# Helepolis_Level1.net
KiCad netlist of a schematic drawn in EAGLE
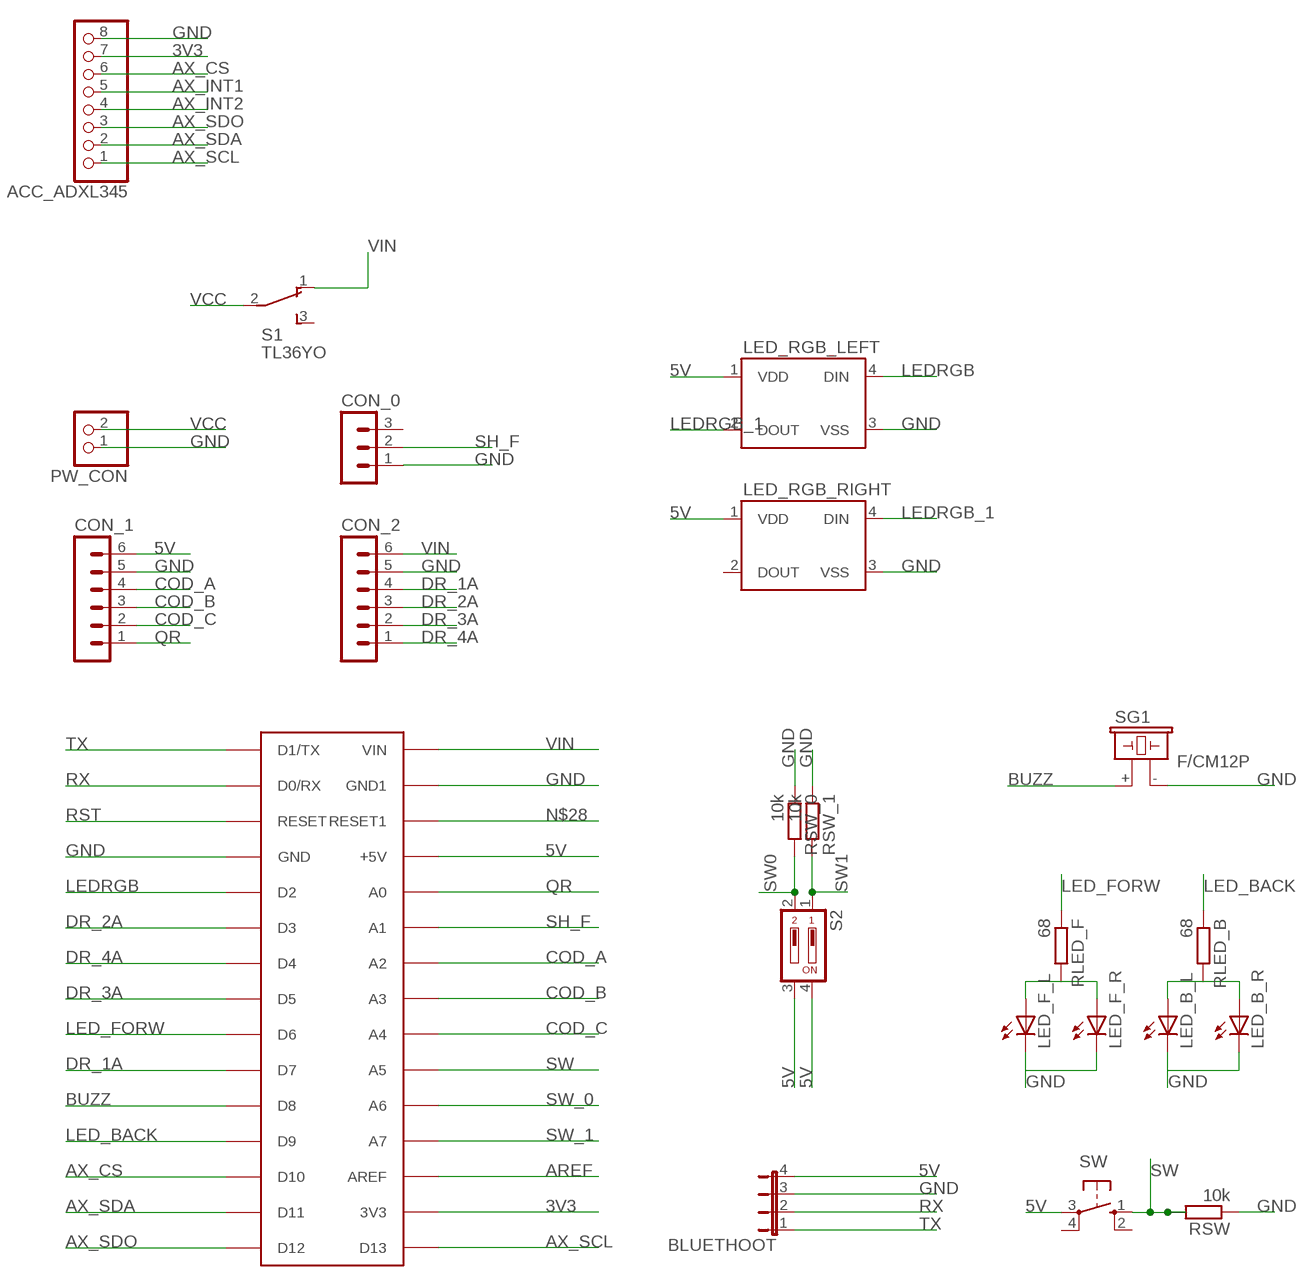
[diagram p0: schematic, sheet 1]

(export (version "E")
  (design (tool "Eeschema 10.0.6"))
  (components
    (comp (ref "ACC_ADXL345")
      (value "PINHD-1X8")
      (footprint "eagle-import:1X08")
      (libsource (lib "eagle-import") (part "PINHD-1X8"))
    )
    (comp (ref "BLUETHOOT")
      (value "JP4E")
      (footprint "eagle-import:JP4")
      (libsource (lib "eagle-import") (part "JP4E"))
    )
    (comp (ref "CON_0")
      (value "MA03-1")
      (footprint "eagle-import:MA03-1")
      (libsource (lib "eagle-import") (part "MA03-1"))
    )
    (comp (ref "CON_1")
      (value "MA06-1")
      (footprint "eagle-import:MA06-1")
      (libsource (lib "eagle-import") (part "MA06-1"))
    )
    (comp (ref "CON_2")
      (value "MA06-1")
      (footprint "eagle-import:MA06-1")
      (libsource (lib "eagle-import") (part "MA06-1"))
    )
    (comp (ref "LED_B_L")
      (value "LED5MM")
      (footprint "eagle-import:LED5MM")
      (libsource (lib "eagle-import") (part "LED5MM"))
    )
    (comp (ref "LED_B_R")
      (value "LED5MM")
      (footprint "eagle-import:LED5MM")
      (libsource (lib "eagle-import") (part "LED5MM"))
    )
    (comp (ref "LED_F_L")
      (value "LED5MM")
      (footprint "eagle-import:LED5MM")
      (libsource (lib "eagle-import") (part "LED5MM"))
    )
    (comp (ref "LED_F_R")
      (value "LED5MM")
      (footprint "eagle-import:LED5MM")
      (libsource (lib "eagle-import") (part "LED5MM"))
    )
    (comp (ref "LED_RGB_LEFT")
      (value "WS2812B")
      (footprint "eagle-import:WS2812B")
      (libsource (lib "eagle-import") (part "WS2812B"))
    )
    (comp (ref "LED_RGB_RIGHT")
      (value "WS2812B")
      (footprint "eagle-import:WS2812B")
      (libsource (lib "eagle-import") (part "WS2812B"))
    )
    (comp (ref "PW_CON")
      (value "PINHD-1X2")
      (footprint "eagle-import:1X02")
      (libsource (lib "eagle-import") (part "PINHD-1X2"))
    )
    (comp (ref "RLED_B")
      (value "68")
      (footprint "eagle-import:R1206")
      (libsource (lib "eagle-import") (part "R-EU_R1206"))
    )
    (comp (ref "RLED_F")
      (value "68")
      (footprint "eagle-import:R1206")
      (libsource (lib "eagle-import") (part "R-EU_R1206"))
    )
    (comp (ref "RSW")
      (value "10k")
      (footprint "eagle-import:R1206")
      (libsource (lib "eagle-import") (part "R-EU_R1206"))
    )
    (comp (ref "RSW_0")
      (value "10k")
      (footprint "eagle-import:R1206")
      (libsource (lib "eagle-import") (part "R-EU_R1206"))
    )
    (comp (ref "RSW_1")
      (value "10k")
      (footprint "eagle-import:R1206")
      (libsource (lib "eagle-import") (part "R-EU_R1206"))
    )
    (comp (ref "S1")
      (value "TL36YO")
      (footprint "eagle-import:TL3XYO")
      (libsource (lib "eagle-import") (part "TL36YO"))
    )
    (comp (ref "S2")
      (value "DP02")
      (footprint "eagle-import:DP-02")
      (fields (field (name "MPN") "MCDP02"))
      (libsource (lib "eagle-import") (part "DP02"))
    )
    (comp (ref "SG1")
      (value "F/CM12P")
      (footprint "eagle-import:F_CM12P")
      (libsource (lib "eagle-import") (part "F/CM12P"))
    )
    (comp (ref "SW")
      (value "10-XX")
      (footprint "eagle-import:B3F-10XX")
      (fields (field (name "MPN") "B3F-1000"))
      (libsource (lib "eagle-import") (part "10-XX"))
    )
    (comp (ref "U$1")
      (value "ARDUINONANO")
      (footprint "eagle-import:PDIP-32")
      (libsource (lib "eagle-import") (part "ARDUINONANO"))
    )
  )
  (nets
    (net (code "1") (name "/3V3") (class "Default")
      (node (ref "ACC_ADXL345") (pin "7") (pinfunction "7_7") (pintype "passive"))
      (node (ref "U$1") (pin "3V3") (pinfunction "3V3_3V3") (pintype "bidirectional"))
    )
    (net (code "2") (name "/5V") (class "Default")
      (node (ref "BLUETHOOT") (pin "4") (pinfunction "4_4") (pintype "passive"))
      (node (ref "CON_1") (pin "6") (pinfunction "6_6") (pintype "passive"))
      (node (ref "LED_RGB_LEFT") (pin "1") (pinfunction "VDD_1") (pintype "power_in"))
      (node (ref "LED_RGB_RIGHT") (pin "1") (pinfunction "VDD_1") (pintype "power_in"))
      (node (ref "S2") (pin "3") (pinfunction "3_3") (pintype "passive"))
      (node (ref "S2") (pin "4") (pinfunction "4_4") (pintype "passive"))
      (node (ref "SW") (pin "3") (pinfunction "P_3") (pintype "passive"))
      (node (ref "U$1") (pin "+5V") (pinfunction "+5V_+5V") (pintype "bidirectional"))
    )
    (net (code "3") (name "/AREF") (class "Default")
      (node (ref "U$1") (pin "AREF") (pinfunction "AREF_AREF") (pintype "bidirectional"))
    )
    (net (code "4") (name "/AX_CS") (class "Default")
      (node (ref "ACC_ADXL345") (pin "6") (pinfunction "6_6") (pintype "passive"))
      (node (ref "U$1") (pin "D10") (pinfunction "D10_D10") (pintype "bidirectional"))
    )
    (net (code "5") (name "/AX_INT1") (class "Default")
      (node (ref "ACC_ADXL345") (pin "5") (pinfunction "5_5") (pintype "passive"))
    )
    (net (code "6") (name "/AX_INT2") (class "Default")
      (node (ref "ACC_ADXL345") (pin "4") (pinfunction "4_4") (pintype "passive"))
    )
    (net (code "7") (name "/AX_SCL") (class "Default")
      (node (ref "ACC_ADXL345") (pin "1") (pinfunction "1_1") (pintype "passive"))
      (node (ref "U$1") (pin "D13") (pinfunction "D13_D13") (pintype "bidirectional"))
    )
    (net (code "8") (name "/AX_SDA") (class "Default")
      (node (ref "ACC_ADXL345") (pin "2") (pinfunction "2_2") (pintype "passive"))
      (node (ref "U$1") (pin "D11") (pinfunction "D11_D11") (pintype "bidirectional"))
    )
    (net (code "9") (name "/AX_SDO") (class "Default")
      (node (ref "ACC_ADXL345") (pin "3") (pinfunction "3_3") (pintype "passive"))
      (node (ref "U$1") (pin "D12") (pinfunction "D12_D12") (pintype "bidirectional"))
    )
    (net (code "10") (name "/BUZZ") (class "Default")
      (node (ref "SG1") (pin "+") (pinfunction "1_+") (pintype "passive"))
      (node (ref "U$1") (pin "D8") (pinfunction "D8_D8") (pintype "bidirectional"))
    )
    (net (code "11") (name "/COD_A") (class "Default")
      (node (ref "CON_1") (pin "4") (pinfunction "4_4") (pintype "passive"))
      (node (ref "U$1") (pin "A2") (pinfunction "A2_A2") (pintype "bidirectional"))
    )
    (net (code "12") (name "/COD_B") (class "Default")
      (node (ref "CON_1") (pin "3") (pinfunction "3_3") (pintype "passive"))
      (node (ref "U$1") (pin "A3") (pinfunction "A3_A3") (pintype "bidirectional"))
    )
    (net (code "13") (name "/COD_C") (class "Default")
      (node (ref "CON_1") (pin "2") (pinfunction "2_2") (pintype "passive"))
      (node (ref "U$1") (pin "A4") (pinfunction "A4_A4") (pintype "bidirectional"))
    )
    (net (code "14") (name "/DR_1A") (class "Default")
      (node (ref "CON_2") (pin "4") (pinfunction "4_4") (pintype "passive"))
      (node (ref "U$1") (pin "D7") (pinfunction "D7_D7") (pintype "bidirectional"))
    )
    (net (code "15") (name "/DR_2A") (class "Default")
      (node (ref "CON_2") (pin "3") (pinfunction "3_3") (pintype "passive"))
      (node (ref "U$1") (pin "D3") (pinfunction "D3_D3") (pintype "bidirectional"))
    )
    (net (code "16") (name "/DR_3A") (class "Default")
      (node (ref "CON_2") (pin "2") (pinfunction "2_2") (pintype "passive"))
      (node (ref "U$1") (pin "D5") (pinfunction "D5_D5") (pintype "bidirectional"))
    )
    (net (code "17") (name "/DR_4A") (class "Default")
      (node (ref "CON_2") (pin "1") (pinfunction "1_1") (pintype "passive"))
      (node (ref "U$1") (pin "D4") (pinfunction "D4_D4") (pintype "bidirectional"))
    )
    (net (code "18") (name "/GND") (class "Default")
      (node (ref "ACC_ADXL345") (pin "8") (pinfunction "8_8") (pintype "passive"))
      (node (ref "BLUETHOOT") (pin "3") (pinfunction "3_3") (pintype "passive"))
      (node (ref "CON_0") (pin "1") (pinfunction "1_1") (pintype "passive"))
      (node (ref "CON_1") (pin "5") (pinfunction "5_5") (pintype "passive"))
      (node (ref "CON_2") (pin "5") (pinfunction "5_5") (pintype "passive"))
      (node (ref "LED_B_L") (pin "K") (pinfunction "C_K") (pintype "passive"))
      (node (ref "LED_B_R") (pin "K") (pinfunction "C_K") (pintype "passive"))
      (node (ref "LED_F_L") (pin "K") (pinfunction "C_K") (pintype "passive"))
      (node (ref "LED_F_R") (pin "K") (pinfunction "C_K") (pintype "passive"))
      (node (ref "LED_RGB_LEFT") (pin "3") (pinfunction "VSS_3") (pintype "power_in"))
      (node (ref "LED_RGB_RIGHT") (pin "3") (pinfunction "VSS_3") (pintype "power_in"))
      (node (ref "PW_CON") (pin "1") (pinfunction "1_1") (pintype "passive"))
      (node (ref "RSW") (pin "1") (pinfunction "1_1") (pintype "passive"))
      (node (ref "RSW_0") (pin "1") (pinfunction "1_1") (pintype "passive"))
      (node (ref "RSW_1") (pin "1") (pinfunction "1_1") (pintype "passive"))
      (node (ref "SG1") (pin "-") (pinfunction "2_-") (pintype "passive"))
      (node (ref "U$1") (pin "GND") (pinfunction "GND_GND") (pintype "bidirectional"))
      (node (ref "U$1") (pin "GND1") (pinfunction "GND1_GND1") (pintype "bidirectional"))
    )
    (net (code "19") (name "/LEDRGB") (class "Default")
      (node (ref "LED_RGB_LEFT") (pin "4") (pinfunction "DIN_4") (pintype "input"))
      (node (ref "U$1") (pin "D2") (pinfunction "D2_D2") (pintype "bidirectional"))
    )
    (net (code "20") (name "/LEDRGB_1") (class "Default")
      (node (ref "LED_RGB_LEFT") (pin "2") (pinfunction "DOUT_2") (pintype "output"))
      (node (ref "LED_RGB_RIGHT") (pin "4") (pinfunction "DIN_4") (pintype "input"))
    )
    (net (code "21") (name "/LED_BACK") (class "Default")
      (node (ref "RLED_B") (pin "1") (pinfunction "1_1") (pintype "passive"))
      (node (ref "U$1") (pin "D9") (pinfunction "D9_D9") (pintype "bidirectional"))
    )
    (net (code "22") (name "/LED_FORW") (class "Default")
      (node (ref "RLED_F") (pin "1") (pinfunction "1_1") (pintype "passive"))
      (node (ref "U$1") (pin "D6") (pinfunction "D6_D6") (pintype "bidirectional"))
    )
    (net (code "23") (name "/N$28") (class "Default")
      (node (ref "U$1") (pin "RESET1") (pinfunction "RESET1_RESET1") (pintype "bidirectional"))
    )
    (net (code "24") (name "/QR") (class "Default")
      (node (ref "CON_1") (pin "1") (pinfunction "1_1") (pintype "passive"))
      (node (ref "U$1") (pin "A0") (pinfunction "A0_A0") (pintype "bidirectional"))
    )
    (net (code "25") (name "/RST") (class "Default")
      (node (ref "U$1") (pin "RESET") (pinfunction "RESET_RESET") (pintype "bidirectional"))
    )
    (net (code "26") (name "/RX") (class "Default")
      (node (ref "BLUETHOOT") (pin "2") (pinfunction "2_2") (pintype "passive"))
      (node (ref "U$1") (pin "D0/RX") (pinfunction "D0/RX_D0/RX") (pintype "bidirectional"))
    )
    (net (code "27") (name "/SH_F") (class "Default")
      (node (ref "CON_0") (pin "2") (pinfunction "2_2") (pintype "passive"))
      (node (ref "U$1") (pin "A1") (pinfunction "A1_A1") (pintype "bidirectional"))
    )
    (net (code "28") (name "/SW") (class "Default")
      (node (ref "RSW") (pin "2") (pinfunction "2_2") (pintype "passive"))
      (node (ref "SW") (pin "1") (pinfunction "S_1") (pintype "passive"))
      (node (ref "U$1") (pin "A5") (pinfunction "A5_A5") (pintype "bidirectional"))
    )
    (net (code "29") (name "/SW0") (class "Default")
      (node (ref "RSW_0") (pin "2") (pinfunction "2_2") (pintype "passive"))
      (node (ref "S2") (pin "2") (pinfunction "2_2") (pintype "passive"))
    )
    (net (code "30") (name "/SW1") (class "Default")
      (node (ref "RSW_1") (pin "2") (pinfunction "2_2") (pintype "passive"))
      (node (ref "S2") (pin "1") (pinfunction "1_1") (pintype "passive"))
    )
    (net (code "31") (name "/SW_0") (class "Default")
      (node (ref "U$1") (pin "A6") (pinfunction "A6_A6") (pintype "bidirectional"))
    )
    (net (code "32") (name "/SW_1") (class "Default")
      (node (ref "U$1") (pin "A7") (pinfunction "A7_A7") (pintype "bidirectional"))
    )
    (net (code "33") (name "/TX") (class "Default")
      (node (ref "BLUETHOOT") (pin "1") (pinfunction "1_1") (pintype "passive"))
      (node (ref "U$1") (pin "D1/TX") (pinfunction "D1/TX_D1/TX") (pintype "bidirectional"))
    )
    (net (code "34") (name "/VCC") (class "Default")
      (node (ref "PW_CON") (pin "2") (pinfunction "2_2") (pintype "passive"))
      (node (ref "S1") (pin "2") (pinfunction "P_2") (pintype "passive"))
    )
    (net (code "35") (name "/VIN") (class "Default")
      (node (ref "CON_2") (pin "6") (pinfunction "6_6") (pintype "passive"))
      (node (ref "S1") (pin "1") (pinfunction "O_1") (pintype "passive"))
      (node (ref "U$1") (pin "VIN") (pinfunction "VIN_VIN") (pintype "bidirectional"))
    )
    (net (code "36") (name "Net-(LED_B_L-PadA)") (class "Default")
      (node (ref "LED_B_L") (pin "A") (pinfunction "A_A") (pintype "passive"))
      (node (ref "LED_B_R") (pin "A") (pinfunction "A_A") (pintype "passive"))
      (node (ref "RLED_B") (pin "2") (pinfunction "2_2") (pintype "passive"))
    )
    (net (code "37") (name "Net-(LED_F_L-PadA)") (class "Default")
      (node (ref "LED_F_L") (pin "A") (pinfunction "A_A") (pintype "passive"))
      (node (ref "LED_F_R") (pin "A") (pinfunction "A_A") (pintype "passive"))
      (node (ref "RLED_F") (pin "2") (pinfunction "2_2") (pintype "passive"))
    )
    (net (code "38") (name "unconnected-(CON_0-Pad3)") (class "Default")
      (node (ref "CON_0") (pin "3") (pinfunction "3_3") (pintype "passive"))
    )
    (net (code "39") (name "unconnected-(LED_RGB_RIGHT-DOUT-Pad2)") (class "Default")
      (node (ref "LED_RGB_RIGHT") (pin "2") (pinfunction "DOUT_2") (pintype "output"))
    )
    (net (code "40") (name "unconnected-(S1-S-Pad3)") (class "Default")
      (node (ref "S1") (pin "3") (pinfunction "S_3") (pintype "passive"))
    )
    (net (code "41") (name "unconnected-(SW-P1-Pad4)") (class "Default")
      (node (ref "SW") (pin "4") (pinfunction "P1_4") (pintype "passive"))
    )
    (net (code "42") (name "unconnected-(SW-S1-Pad2)") (class "Default")
      (node (ref "SW") (pin "2") (pinfunction "S1_2") (pintype "passive"))
    )
  )
)
